# tank_adapter_power.net
KiCad netlist of a schematic drawn in Altium Designer
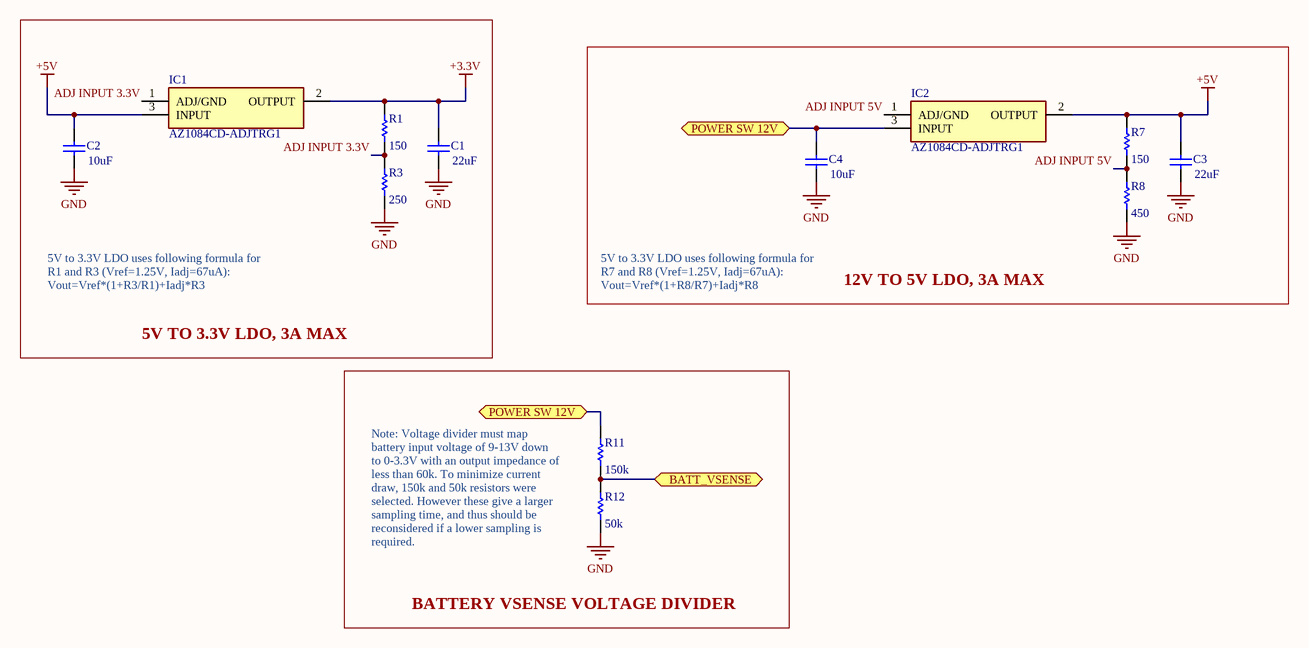
[diagram p0: tank_adapter_power.SchDoc]

(export (version "E")
  (design (tool "Eeschema 10.0.6"))
  (components
    (comp (ref "C1")
      (value "22uF")
      (footprint "C0805")
      (description "Capacitor")
      (fields (field (name "Comment") "Cap") (field (name "PUBLISHER") "Altium Limited"))
      (libsource (lib "Miscellaneous Devices") (part "Cap"))
    )
    (comp (ref "C2")
      (value "10uF")
      (footprint "C0805")
      (description "Capacitor")
      (fields (field (name "Comment") "Cap") (field (name "PUBLISHER") "Altium Limited"))
      (libsource (lib "Miscellaneous Devices") (part "Cap"))
    )
    (comp (ref "C3")
      (value "22uF")
      (footprint "C0805")
      (description "Capacitor")
      (fields (field (name "Comment") "Cap") (field (name "PUBLISHER") "Altium Limited"))
      (libsource (lib "Miscellaneous Devices") (part "Cap"))
    )
    (comp (ref "C4")
      (value "10uF")
      (footprint "C0805")
      (description "Capacitor")
      (fields (field (name "Comment") "Cap") (field (name "PUBLISHER") "Altium Limited"))
      (libsource (lib "Miscellaneous Devices") (part "Cap"))
    )
    (comp (ref "IC1")
      (value "AZ1084CD-ADJTRG1")
      (footprint "SamacSys:AZ1084CDADJTRG1")
      (description "Integrated Circuit")
      (fields (field (name "MOUSER2 PART NUMBER") "621-AZ1084CD-ADJTRG1"))
      (libsource (lib "*") (part "AZ1084CD-ADJTRG1"))
    )
    (comp (ref "IC2")
      (value "AZ1084CD-ADJTRG1")
      (footprint "SamacSys:AZ1084CDADJTRG1")
      (description "Integrated Circuit")
      (fields (field (name "MOUSER2 PART NUMBER") "621-AZ1084CD-ADJTRG1"))
      (libsource (lib "*") (part "AZ1084CD-ADJTRG1"))
    )
    (comp (ref "R1")
      (value "150")
      (footprint "6-0805_M")
      (description "Resistor")
      (fields (field (name "Comment") "Res1") (field (name "PUBLISHER") "Altium Limited"))
      (libsource (lib "Miscellaneous Devices") (part "Res1"))
    )
    (comp (ref "R3")
      (value "250")
      (footprint "6-0805_M")
      (description "Resistor")
      (fields (field (name "Comment") "Res1") (field (name "PUBLISHER") "Altium Limited"))
      (libsource (lib "Miscellaneous Devices") (part "Res1"))
    )
    (comp (ref "R7")
      (value "150")
      (footprint "6-0805_M")
      (description "Resistor")
      (fields (field (name "Comment") "Res1") (field (name "PUBLISHER") "Altium Limited"))
      (libsource (lib "Miscellaneous Devices") (part "Res1"))
    )
    (comp (ref "R8")
      (value "450")
      (footprint "6-0805_M")
      (description "Resistor")
      (fields (field (name "Comment") "Res1") (field (name "PUBLISHER") "Altium Limited"))
      (libsource (lib "Miscellaneous Devices") (part "Res1"))
    )
    (comp (ref "R11")
      (value "150k")
      (footprint "6-0805_M")
      (description "Resistor")
      (fields (field (name "Comment") "Res1") (field (name "PUBLISHER") "Altium Limited"))
      (libsource (lib "Miscellaneous Devices") (part "Res1"))
    )
    (comp (ref "R12")
      (value "50k")
      (footprint "6-0805_M")
      (description "Resistor")
      (fields (field (name "Comment") "Res1") (field (name "PUBLISHER") "Altium Limited"))
      (libsource (lib "Miscellaneous Devices") (part "Res1"))
    )
  )
  (nets
    (net (code "1") (name "+3.3V") (class "Default")
      (node (ref "C1") (pin "2") (pinfunction "2_2") (pintype "passive"))
      (node (ref "IC1") (pin "2") (pinfunction "OUTPUT_2") (pintype "passive"))
      (node (ref "R1") (pin "2") (pinfunction "2_2") (pintype "passive"))
    )
    (net (code "2") (name "+5V") (class "Default")
      (node (ref "C2") (pin "2") (pinfunction "2_2") (pintype "passive"))
      (node (ref "C3") (pin "2") (pinfunction "2_2") (pintype "passive"))
      (node (ref "IC1") (pin "3") (pinfunction "INPUT_3") (pintype "passive"))
      (node (ref "IC2") (pin "2") (pinfunction "OUTPUT_2") (pintype "passive"))
      (node (ref "R7") (pin "2") (pinfunction "2_2") (pintype "passive"))
    )
    (net (code "3") (name "/ADJ INPUT 3.3V") (class "Default")
      (node (ref "IC1") (pin "1") (pinfunction "ADJ/GND_1") (pintype "passive"))
      (node (ref "R1") (pin "1") (pinfunction "1_1") (pintype "passive"))
      (node (ref "R3") (pin "2") (pinfunction "2_2") (pintype "passive"))
    )
    (net (code "4") (name "/ADJ INPUT 5V") (class "Default")
      (node (ref "IC2") (pin "1") (pinfunction "ADJ/GND_1") (pintype "passive"))
      (node (ref "R7") (pin "1") (pinfunction "1_1") (pintype "passive"))
      (node (ref "R8") (pin "2") (pinfunction "2_2") (pintype "passive"))
    )
    (net (code "5") (name "/BATT_VSENSE") (class "Default")
      (node (ref "R11") (pin "1") (pinfunction "1_1") (pintype "passive"))
      (node (ref "R12") (pin "2") (pinfunction "2_2") (pintype "passive"))
    )
    (net (code "6") (name "/POWER SW 12V") (class "Default")
      (node (ref "C4") (pin "2") (pinfunction "2_2") (pintype "passive"))
      (node (ref "IC2") (pin "3") (pinfunction "INPUT_3") (pintype "passive"))
      (node (ref "R11") (pin "2") (pinfunction "2_2") (pintype "passive"))
    )
    (net (code "7") (name "GND") (class "Default")
      (node (ref "C1") (pin "1") (pinfunction "1_1") (pintype "passive"))
      (node (ref "C2") (pin "1") (pinfunction "1_1") (pintype "passive"))
      (node (ref "C3") (pin "1") (pinfunction "1_1") (pintype "passive"))
      (node (ref "C4") (pin "1") (pinfunction "1_1") (pintype "passive"))
      (node (ref "R12") (pin "1") (pinfunction "1_1") (pintype "passive"))
      (node (ref "R3") (pin "1") (pinfunction "1_1") (pintype "passive"))
      (node (ref "R8") (pin "1") (pinfunction "1_1") (pintype "passive"))
    )
  )
)
